# 8500_ADC_X.net
KiCad netlist of a schematic drawn in Altium Designer
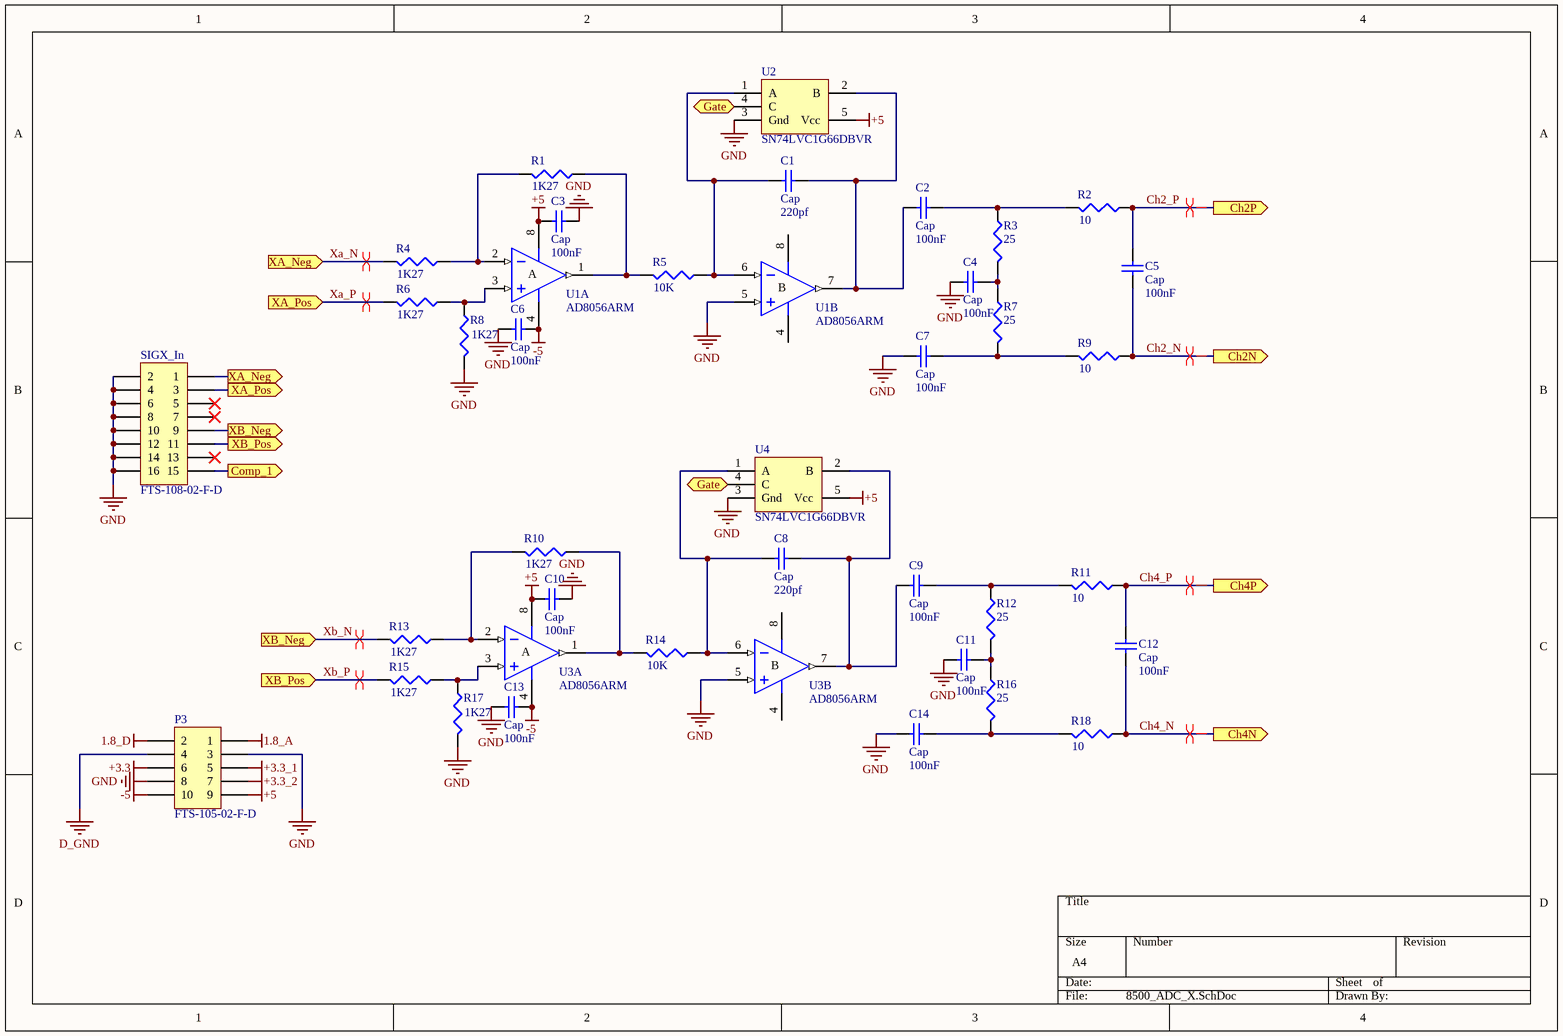
[diagram p0: 8500_ADC_X.SchDoc]

(export (version "E")
  (design (tool "Eeschema 10.0.6"))
  (components
    (comp (ref "C1")
      (value "Cap")
      (footprint "0402")
      (description "Capacitor")
      (fields (field (name "ALTIUM_VALUE") "220pf") (field (name "PUBLISHER") "Altium Limited"))
      (libsource (lib "Miscellaneous Devices") (part "Cap"))
    )
    (comp (ref "C2")
      (value "Cap")
      (footprint "0402")
      (description "Capacitor")
      (fields (field (name "ALTIUM_VALUE") "100nF") (field (name "PUBLISHER") "Altium Limited"))
      (libsource (lib "Miscellaneous Devices") (part "Cap"))
    )
    (comp (ref "C3")
      (value "Cap")
      (footprint "0402")
      (description "Capacitor")
      (fields (field (name "ALTIUM_VALUE") "100nF") (field (name "PUBLISHER") "Altium Limited"))
      (libsource (lib "Miscellaneous Devices") (part "Cap"))
    )
    (comp (ref "C4")
      (value "Cap")
      (footprint "0402")
      (description "Capacitor")
      (fields (field (name "ALTIUM_VALUE") "100nF") (field (name "PUBLISHER") "Altium Limited"))
      (libsource (lib "Miscellaneous Devices") (part "Cap"))
    )
    (comp (ref "C5")
      (value "Cap")
      (footprint "0402")
      (description "Capacitor")
      (fields (field (name "ALTIUM_VALUE") "100nF") (field (name "PUBLISHER") "Altium Limited"))
      (libsource (lib "Miscellaneous Devices") (part "Cap"))
    )
    (comp (ref "C6")
      (value "Cap")
      (footprint "0402")
      (description "Capacitor")
      (fields (field (name "ALTIUM_VALUE") "100nF") (field (name "PUBLISHER") "Altium Limited"))
      (libsource (lib "Miscellaneous Devices") (part "Cap"))
    )
    (comp (ref "C7")
      (value "Cap")
      (footprint "0402")
      (description "Capacitor")
      (fields (field (name "ALTIUM_VALUE") "100nF") (field (name "PUBLISHER") "Altium Limited"))
      (libsource (lib "Miscellaneous Devices") (part "Cap"))
    )
    (comp (ref "C8")
      (value "Cap")
      (footprint "0402")
      (description "Capacitor")
      (fields (field (name "ALTIUM_VALUE") "220pf") (field (name "PUBLISHER") "Altium Limited"))
      (libsource (lib "Miscellaneous Devices") (part "Cap"))
    )
    (comp (ref "C9")
      (value "Cap")
      (footprint "0402")
      (description "Capacitor")
      (fields (field (name "ALTIUM_VALUE") "100nF") (field (name "PUBLISHER") "Altium Limited"))
      (libsource (lib "Miscellaneous Devices") (part "Cap"))
    )
    (comp (ref "C10")
      (value "Cap")
      (footprint "0402")
      (description "Capacitor")
      (fields (field (name "ALTIUM_VALUE") "100nF") (field (name "PUBLISHER") "Altium Limited"))
      (libsource (lib "Miscellaneous Devices") (part "Cap"))
    )
    (comp (ref "C11")
      (value "Cap")
      (footprint "0402")
      (description "Capacitor")
      (fields (field (name "ALTIUM_VALUE") "100nF") (field (name "PUBLISHER") "Altium Limited"))
      (libsource (lib "Miscellaneous Devices") (part "Cap"))
    )
    (comp (ref "C12")
      (value "Cap")
      (footprint "0402")
      (description "Capacitor")
      (fields (field (name "ALTIUM_VALUE") "100nF") (field (name "PUBLISHER") "Altium Limited"))
      (libsource (lib "Miscellaneous Devices") (part "Cap"))
    )
    (comp (ref "C13")
      (value "Cap")
      (footprint "0402")
      (description "Capacitor")
      (fields (field (name "ALTIUM_VALUE") "100nF") (field (name "PUBLISHER") "Altium Limited"))
      (libsource (lib "Miscellaneous Devices") (part "Cap"))
    )
    (comp (ref "C14")
      (value "Cap")
      (footprint "0402")
      (description "Capacitor")
      (fields (field (name "ALTIUM_VALUE") "100nF") (field (name "PUBLISHER") "Altium Limited"))
      (libsource (lib "Miscellaneous Devices") (part "Cap"))
    )
    (comp (ref "P3")
      (value "FTS-105-02-F-D")
      (footprint "MHDR2X5")
      (libsource (lib "Int_Lib1") (part "FTR-105-01-D"))
    )
    (comp (ref "R1")
      (value "1K27")
      (footprint "0402")
      (description "Resistor")
      (fields (field (name "Comment") "Res3") (field (name "PUBLISHER") "Altium Limited"))
      (libsource (lib "Miscellaneous Devices") (part "Res3"))
    )
    (comp (ref "R2")
      (value "10")
      (footprint "0402")
      (description "Resistor")
      (fields (field (name "Comment") "Res3") (field (name "PUBLISHER") "Altium Limited"))
      (libsource (lib "Miscellaneous Devices") (part "Res3"))
    )
    (comp (ref "R3")
      (value "25")
      (footprint "0402")
      (description "Resistor")
      (fields (field (name "Comment") "Res3") (field (name "PUBLISHER") "Altium Limited"))
      (libsource (lib "Miscellaneous Devices") (part "Res3"))
    )
    (comp (ref "R4")
      (value "1K27")
      (footprint "0402")
      (description "Resistor")
      (fields (field (name "Comment") "Res3") (field (name "PUBLISHER") "Altium Limited"))
      (libsource (lib "Miscellaneous Devices") (part "Res3"))
    )
    (comp (ref "R5")
      (value "10K")
      (footprint "0402")
      (description "Resistor")
      (fields (field (name "Comment") "Res3") (field (name "PUBLISHER") "Altium Limited"))
      (libsource (lib "Miscellaneous Devices") (part "Res3"))
    )
    (comp (ref "R6")
      (value "1K27")
      (footprint "0402")
      (description "Resistor")
      (fields (field (name "Comment") "Res3") (field (name "PUBLISHER") "Altium Limited"))
      (libsource (lib "Miscellaneous Devices") (part "Res3"))
    )
    (comp (ref "R7")
      (value "25")
      (footprint "0402")
      (description "Resistor")
      (fields (field (name "Comment") "Res3") (field (name "PUBLISHER") "Altium Limited"))
      (libsource (lib "Miscellaneous Devices") (part "Res3"))
    )
    (comp (ref "R8")
      (value "1K27")
      (footprint "0402")
      (description "Resistor")
      (fields (field (name "Comment") "Res3") (field (name "PUBLISHER") "Altium Limited"))
      (libsource (lib "Miscellaneous Devices") (part "Res3"))
    )
    (comp (ref "R9")
      (value "10")
      (footprint "0402")
      (description "Resistor")
      (fields (field (name "Comment") "Res3") (field (name "PUBLISHER") "Altium Limited"))
      (libsource (lib "Miscellaneous Devices") (part "Res3"))
    )
    (comp (ref "R10")
      (value "1K27")
      (footprint "0402")
      (description "Resistor")
      (fields (field (name "Comment") "Res3") (field (name "PUBLISHER") "Altium Limited"))
      (libsource (lib "Miscellaneous Devices") (part "Res3"))
    )
    (comp (ref "R11")
      (value "10")
      (footprint "0402")
      (description "Resistor")
      (fields (field (name "Comment") "Res3") (field (name "PUBLISHER") "Altium Limited"))
      (libsource (lib "Miscellaneous Devices") (part "Res3"))
    )
    (comp (ref "R12")
      (value "25")
      (footprint "0402")
      (description "Resistor")
      (fields (field (name "Comment") "Res3") (field (name "PUBLISHER") "Altium Limited"))
      (libsource (lib "Miscellaneous Devices") (part "Res3"))
    )
    (comp (ref "R13")
      (value "1K27")
      (footprint "0402")
      (description "Resistor")
      (fields (field (name "Comment") "Res3") (field (name "PUBLISHER") "Altium Limited"))
      (libsource (lib "Miscellaneous Devices") (part "Res3"))
    )
    (comp (ref "R14")
      (value "10K")
      (footprint "0402")
      (description "Resistor")
      (fields (field (name "Comment") "Res3") (field (name "PUBLISHER") "Altium Limited"))
      (libsource (lib "Miscellaneous Devices") (part "Res3"))
    )
    (comp (ref "R15")
      (value "1K27")
      (footprint "0402")
      (description "Resistor")
      (fields (field (name "Comment") "Res3") (field (name "PUBLISHER") "Altium Limited"))
      (libsource (lib "Miscellaneous Devices") (part "Res3"))
    )
    (comp (ref "R16")
      (value "25")
      (footprint "0402")
      (description "Resistor")
      (fields (field (name "Comment") "Res3") (field (name "PUBLISHER") "Altium Limited"))
      (libsource (lib "Miscellaneous Devices") (part "Res3"))
    )
    (comp (ref "R17")
      (value "1K27")
      (footprint "0402")
      (description "Resistor")
      (fields (field (name "Comment") "Res3") (field (name "PUBLISHER") "Altium Limited"))
      (libsource (lib "Miscellaneous Devices") (part "Res3"))
    )
    (comp (ref "R18")
      (value "10")
      (footprint "0402")
      (description "Resistor")
      (fields (field (name "Comment") "Res3") (field (name "PUBLISHER") "Altium Limited"))
      (libsource (lib "Miscellaneous Devices") (part "Res3"))
    )
    (comp (ref "SIGX_In")
      (value "FTS-108-02-F-D")
      (footprint "MHDR2X8")
      (libsource (lib "Int_Lib1") (part "FTR-108-01-D"))
    )
    (comp (ref "U1")
      (value "AD8056ARM")
      (footprint "RM-8")
      (description "Low Cost, 300MHz Voltage Feedback Amplifier")
      (fields (field (name "PUBLISHER") "Altium Limited"))
      (libsource (lib "AD Operational Amplifier") (part "AD8056ARM"))
    )
    (comp (ref "U2")
      (value "SN74LVC1G66DBVR")
      (footprint "SOT23-5")
      (libsource (lib "Int_Lib1") (part "SN74LVC1G66DBVR"))
    )
    (comp (ref "U3")
      (value "AD8056ARM")
      (footprint "RM-8")
      (description "Low Cost, 300MHz Voltage Feedback Amplifier")
      (fields (field (name "PUBLISHER") "Altium Limited"))
      (libsource (lib "AD Operational Amplifier") (part "AD8056ARM"))
    )
    (comp (ref "U4")
      (value "SN74LVC1G66DBVR")
      (footprint "SOT23-5")
      (libsource (lib "Int_Lib1") (part "SN74LVC1G66DBVR"))
    )
  )
  (nets
    (net (code "1") (name "+3.3") (class "Default")
      (node (ref "P3") (pin "6") (pinfunction "6_6") (pintype "passive"))
    )
    (net (code "2") (name "+3.3_1") (class "Default")
      (node (ref "P3") (pin "5") (pinfunction "5_5") (pintype "passive"))
    )
    (net (code "3") (name "+3.3_2") (class "Default")
      (node (ref "P3") (pin "7") (pinfunction "7_7") (pintype "passive"))
    )
    (net (code "4") (name "+5") (class "Default")
      (node (ref "C10") (pin "1") (pinfunction "1_1") (pintype "passive"))
      (node (ref "C3") (pin "1") (pinfunction "1_1") (pintype "passive"))
      (node (ref "P3") (pin "9") (pinfunction "9_9") (pintype "passive"))
      (node (ref "U1") (pin "8") (pinfunction "V+_8") (pintype "power_in"))
      (node (ref "U2") (pin "5") (pinfunction "Vcc_5") (pintype "passive"))
      (node (ref "U3") (pin "8") (pinfunction "V+_8") (pintype "power_in"))
      (node (ref "U4") (pin "5") (pinfunction "Vcc_5") (pintype "passive"))
    )
    (net (code "5") (name "-5") (class "Default")
      (node (ref "C13") (pin "2") (pinfunction "2_2") (pintype "passive"))
      (node (ref "C6") (pin "2") (pinfunction "2_2") (pintype "passive"))
      (node (ref "P3") (pin "10") (pinfunction "10_10") (pintype "passive"))
      (node (ref "U1") (pin "4") (pinfunction "V-_4") (pintype "power_in"))
      (node (ref "U3") (pin "4") (pinfunction "V-_4") (pintype "power_in"))
    )
    (net (code "6") (name "/Ch2_N") (class "Default")
      (node (ref "C5") (pin "1") (pinfunction "1_1") (pintype "passive"))
      (node (ref "R9") (pin "1") (pinfunction "1_1") (pintype "passive"))
    )
    (net (code "7") (name "/Ch2_P") (class "Default")
      (node (ref "C5") (pin "2") (pinfunction "2_2") (pintype "passive"))
      (node (ref "R2") (pin "1") (pinfunction "1_1") (pintype "passive"))
    )
    (net (code "8") (name "/Ch4_N") (class "Default")
      (node (ref "C12") (pin "1") (pinfunction "1_1") (pintype "passive"))
      (node (ref "R18") (pin "1") (pinfunction "1_1") (pintype "passive"))
    )
    (net (code "9") (name "/Ch4_P") (class "Default")
      (node (ref "C12") (pin "2") (pinfunction "2_2") (pintype "passive"))
      (node (ref "R11") (pin "1") (pinfunction "1_1") (pintype "passive"))
    )
    (net (code "10") (name "/Comp_1") (class "Default")
      (node (ref "SIGX_In") (pin "15") (pinfunction "15_15") (pintype "passive"))
    )
    (net (code "11") (name "/Gate") (class "Default")
      (node (ref "U2") (pin "4") (pinfunction "C_4") (pintype "passive"))
      (node (ref "U4") (pin "4") (pinfunction "C_4") (pintype "passive"))
    )
    (net (code "12") (name "/Xa_N") (class "Default")
      (node (ref "R4") (pin "2") (pinfunction "2_2") (pintype "passive"))
      (node (ref "SIGX_In") (pin "1") (pinfunction "1_1") (pintype "passive"))
    )
    (net (code "13") (name "/Xa_P") (class "Default")
      (node (ref "R6") (pin "2") (pinfunction "2_2") (pintype "passive"))
      (node (ref "SIGX_In") (pin "3") (pinfunction "3_3") (pintype "passive"))
    )
    (net (code "14") (name "/Xb_N") (class "Default")
      (node (ref "R13") (pin "2") (pinfunction "2_2") (pintype "passive"))
      (node (ref "SIGX_In") (pin "9") (pinfunction "9_9") (pintype "passive"))
    )
    (net (code "15") (name "/Xb_P") (class "Default")
      (node (ref "R15") (pin "2") (pinfunction "2_2") (pintype "passive"))
      (node (ref "SIGX_In") (pin "11") (pinfunction "11_11") (pintype "passive"))
    )
    (net (code "16") (name "1.8_A") (class "Default")
      (node (ref "P3") (pin "1") (pinfunction "1_1") (pintype "passive"))
    )
    (net (code "17") (name "1.8_D") (class "Default")
      (node (ref "P3") (pin "2") (pinfunction "2_2") (pintype "passive"))
    )
    (net (code "18") (name "D_GND") (class "Default")
      (node (ref "P3") (pin "4") (pinfunction "4_4") (pintype "passive"))
    )
    (net (code "19") (name "GND") (class "Default")
      (node (ref "C10") (pin "2") (pinfunction "2_2") (pintype "passive"))
      (node (ref "C11") (pin "1") (pinfunction "1_1") (pintype "passive"))
      (node (ref "C13") (pin "1") (pinfunction "1_1") (pintype "passive"))
      (node (ref "C14") (pin "1") (pinfunction "1_1") (pintype "passive"))
      (node (ref "C3") (pin "2") (pinfunction "2_2") (pintype "passive"))
      (node (ref "C4") (pin "1") (pinfunction "1_1") (pintype "passive"))
      (node (ref "C6") (pin "1") (pinfunction "1_1") (pintype "passive"))
      (node (ref "C7") (pin "1") (pinfunction "1_1") (pintype "passive"))
      (node (ref "P3") (pin "3") (pinfunction "3_3") (pintype "passive"))
      (node (ref "P3") (pin "8") (pinfunction "8_8") (pintype "passive"))
      (node (ref "R17") (pin "2") (pinfunction "2_2") (pintype "passive"))
      (node (ref "R8") (pin "2") (pinfunction "2_2") (pintype "passive"))
      (node (ref "SIGX_In") (pin "10") (pinfunction "10_10") (pintype "passive"))
      (node (ref "SIGX_In") (pin "12") (pinfunction "12_12") (pintype "passive"))
      (node (ref "SIGX_In") (pin "14") (pinfunction "14_14") (pintype "passive"))
      (node (ref "SIGX_In") (pin "16") (pinfunction "16_16") (pintype "passive"))
      (node (ref "SIGX_In") (pin "2") (pinfunction "2_2") (pintype "passive"))
      (node (ref "SIGX_In") (pin "4") (pinfunction "4_4") (pintype "passive"))
      (node (ref "SIGX_In") (pin "6") (pinfunction "6_6") (pintype "passive"))
      (node (ref "SIGX_In") (pin "8") (pinfunction "8_8") (pintype "passive"))
      (node (ref "U1") (pin "5") (pinfunction "IN+_5") (pintype "input"))
      (node (ref "U2") (pin "3") (pinfunction "Gnd_3") (pintype "passive"))
      (node (ref "U3") (pin "5") (pinfunction "IN+_5") (pintype "input"))
      (node (ref "U4") (pin "3") (pinfunction "Gnd_3") (pintype "passive"))
    )
    (net (code "20") (name "Net-(C2-Pad2)") (class "Default")
      (node (ref "C2") (pin "2") (pinfunction "2_2") (pintype "passive"))
      (node (ref "R2") (pin "2") (pinfunction "2_2") (pintype "passive"))
      (node (ref "R3") (pin "1") (pinfunction "1_1") (pintype "passive"))
    )
    (net (code "21") (name "Net-(C4-Pad2)") (class "Default")
      (node (ref "C4") (pin "2") (pinfunction "2_2") (pintype "passive"))
      (node (ref "R3") (pin "2") (pinfunction "2_2") (pintype "passive"))
      (node (ref "R7") (pin "1") (pinfunction "1_1") (pintype "passive"))
    )
    (net (code "22") (name "Net-(C7-Pad2)") (class "Default")
      (node (ref "C7") (pin "2") (pinfunction "2_2") (pintype "passive"))
      (node (ref "R7") (pin "2") (pinfunction "2_2") (pintype "passive"))
      (node (ref "R9") (pin "2") (pinfunction "2_2") (pintype "passive"))
    )
    (net (code "23") (name "Net-(C9-Pad2)") (class "Default")
      (node (ref "C9") (pin "2") (pinfunction "2_2") (pintype "passive"))
      (node (ref "R11") (pin "2") (pinfunction "2_2") (pintype "passive"))
      (node (ref "R12") (pin "1") (pinfunction "1_1") (pintype "passive"))
    )
    (net (code "24") (name "Net-(C11-Pad2)") (class "Default")
      (node (ref "C11") (pin "2") (pinfunction "2_2") (pintype "passive"))
      (node (ref "R12") (pin "2") (pinfunction "2_2") (pintype "passive"))
      (node (ref "R16") (pin "1") (pinfunction "1_1") (pintype "passive"))
    )
    (net (code "25") (name "Net-(C14-Pad2)") (class "Default")
      (node (ref "C14") (pin "2") (pinfunction "2_2") (pintype "passive"))
      (node (ref "R16") (pin "2") (pinfunction "2_2") (pintype "passive"))
      (node (ref "R18") (pin "2") (pinfunction "2_2") (pintype "passive"))
    )
    (net (code "26") (name "Net-(U1A-IN+)") (class "Default")
      (node (ref "R6") (pin "1") (pinfunction "1_1") (pintype "passive"))
      (node (ref "R8") (pin "1") (pinfunction "1_1") (pintype "passive"))
      (node (ref "U1") (pin "3") (pinfunction "IN+_3") (pintype "input"))
    )
    (net (code "27") (name "Net-(U1A-IN-)") (class "Default")
      (node (ref "R1") (pin "2") (pinfunction "2_2") (pintype "passive"))
      (node (ref "R4") (pin "1") (pinfunction "1_1") (pintype "passive"))
      (node (ref "U1") (pin "2") (pinfunction "IN-_2") (pintype "input"))
    )
    (net (code "28") (name "Net-(U1A-OUT)") (class "Default")
      (node (ref "R1") (pin "1") (pinfunction "1_1") (pintype "passive"))
      (node (ref "R5") (pin "2") (pinfunction "2_2") (pintype "passive"))
      (node (ref "U1") (pin "1") (pinfunction "OUT_1") (pintype "output"))
    )
    (net (code "29") (name "Net-(U1B-IN-)") (class "Default")
      (node (ref "C1") (pin "1") (pinfunction "1_1") (pintype "passive"))
      (node (ref "R5") (pin "1") (pinfunction "1_1") (pintype "passive"))
      (node (ref "U1") (pin "6") (pinfunction "IN-_6") (pintype "input"))
      (node (ref "U2") (pin "1") (pinfunction "A_1") (pintype "passive"))
    )
    (net (code "30") (name "Net-(U1B-OUT)") (class "Default")
      (node (ref "C1") (pin "2") (pinfunction "2_2") (pintype "passive"))
      (node (ref "C2") (pin "1") (pinfunction "1_1") (pintype "passive"))
      (node (ref "U1") (pin "7") (pinfunction "OUT_7") (pintype "output"))
      (node (ref "U2") (pin "2") (pinfunction "B_2") (pintype "passive"))
    )
    (net (code "31") (name "Net-(U3A-IN+)") (class "Default")
      (node (ref "R15") (pin "1") (pinfunction "1_1") (pintype "passive"))
      (node (ref "R17") (pin "1") (pinfunction "1_1") (pintype "passive"))
      (node (ref "U3") (pin "3") (pinfunction "IN+_3") (pintype "input"))
    )
    (net (code "32") (name "Net-(U3A-IN-)") (class "Default")
      (node (ref "R10") (pin "2") (pinfunction "2_2") (pintype "passive"))
      (node (ref "R13") (pin "1") (pinfunction "1_1") (pintype "passive"))
      (node (ref "U3") (pin "2") (pinfunction "IN-_2") (pintype "input"))
    )
    (net (code "33") (name "Net-(U3A-OUT)") (class "Default")
      (node (ref "R10") (pin "1") (pinfunction "1_1") (pintype "passive"))
      (node (ref "R14") (pin "2") (pinfunction "2_2") (pintype "passive"))
      (node (ref "U3") (pin "1") (pinfunction "OUT_1") (pintype "output"))
    )
    (net (code "34") (name "Net-(U3B-IN-)") (class "Default")
      (node (ref "C8") (pin "1") (pinfunction "1_1") (pintype "passive"))
      (node (ref "R14") (pin "1") (pinfunction "1_1") (pintype "passive"))
      (node (ref "U3") (pin "6") (pinfunction "IN-_6") (pintype "input"))
      (node (ref "U4") (pin "1") (pinfunction "A_1") (pintype "passive"))
    )
    (net (code "35") (name "Net-(U3B-OUT)") (class "Default")
      (node (ref "C8") (pin "2") (pinfunction "2_2") (pintype "passive"))
      (node (ref "C9") (pin "1") (pinfunction "1_1") (pintype "passive"))
      (node (ref "U3") (pin "7") (pinfunction "OUT_7") (pintype "output"))
      (node (ref "U4") (pin "2") (pinfunction "B_2") (pintype "passive"))
    )
    (net (code "36") (name "unconnected-(SIGX_In-Pad5)") (class "Default")
      (node (ref "SIGX_In") (pin "5") (pinfunction "5_5") (pintype "passive+no_connect"))
    )
    (net (code "37") (name "unconnected-(SIGX_In-Pad7)") (class "Default")
      (node (ref "SIGX_In") (pin "7") (pinfunction "7_7") (pintype "passive+no_connect"))
    )
    (net (code "38") (name "unconnected-(SIGX_In-Pad13)") (class "Default")
      (node (ref "SIGX_In") (pin "13") (pinfunction "13_13") (pintype "passive+no_connect"))
    )
    (net (code "39") (name "unconnected-(U1B-V+-Pad8)") (class "Default")
      (node (ref "U1") (pin "8") (pinfunction "V+_8") (pintype "power_in"))
    )
    (net (code "40") (name "unconnected-(U1B-V--Pad4)") (class "Default")
      (node (ref "U1") (pin "4") (pinfunction "V-_4") (pintype "power_in"))
    )
    (net (code "41") (name "unconnected-(U3B-V+-Pad8)") (class "Default")
      (node (ref "U3") (pin "8") (pinfunction "V+_8") (pintype "power_in"))
    )
    (net (code "42") (name "unconnected-(U3B-V--Pad4)") (class "Default")
      (node (ref "U3") (pin "4") (pinfunction "V-_4") (pintype "power_in"))
    )
  )
)
